# KegWasher_1_10_HCRelay_Schematic_EasyEDA.net
KiCad netlist of a schematic drawn in EasyEDA
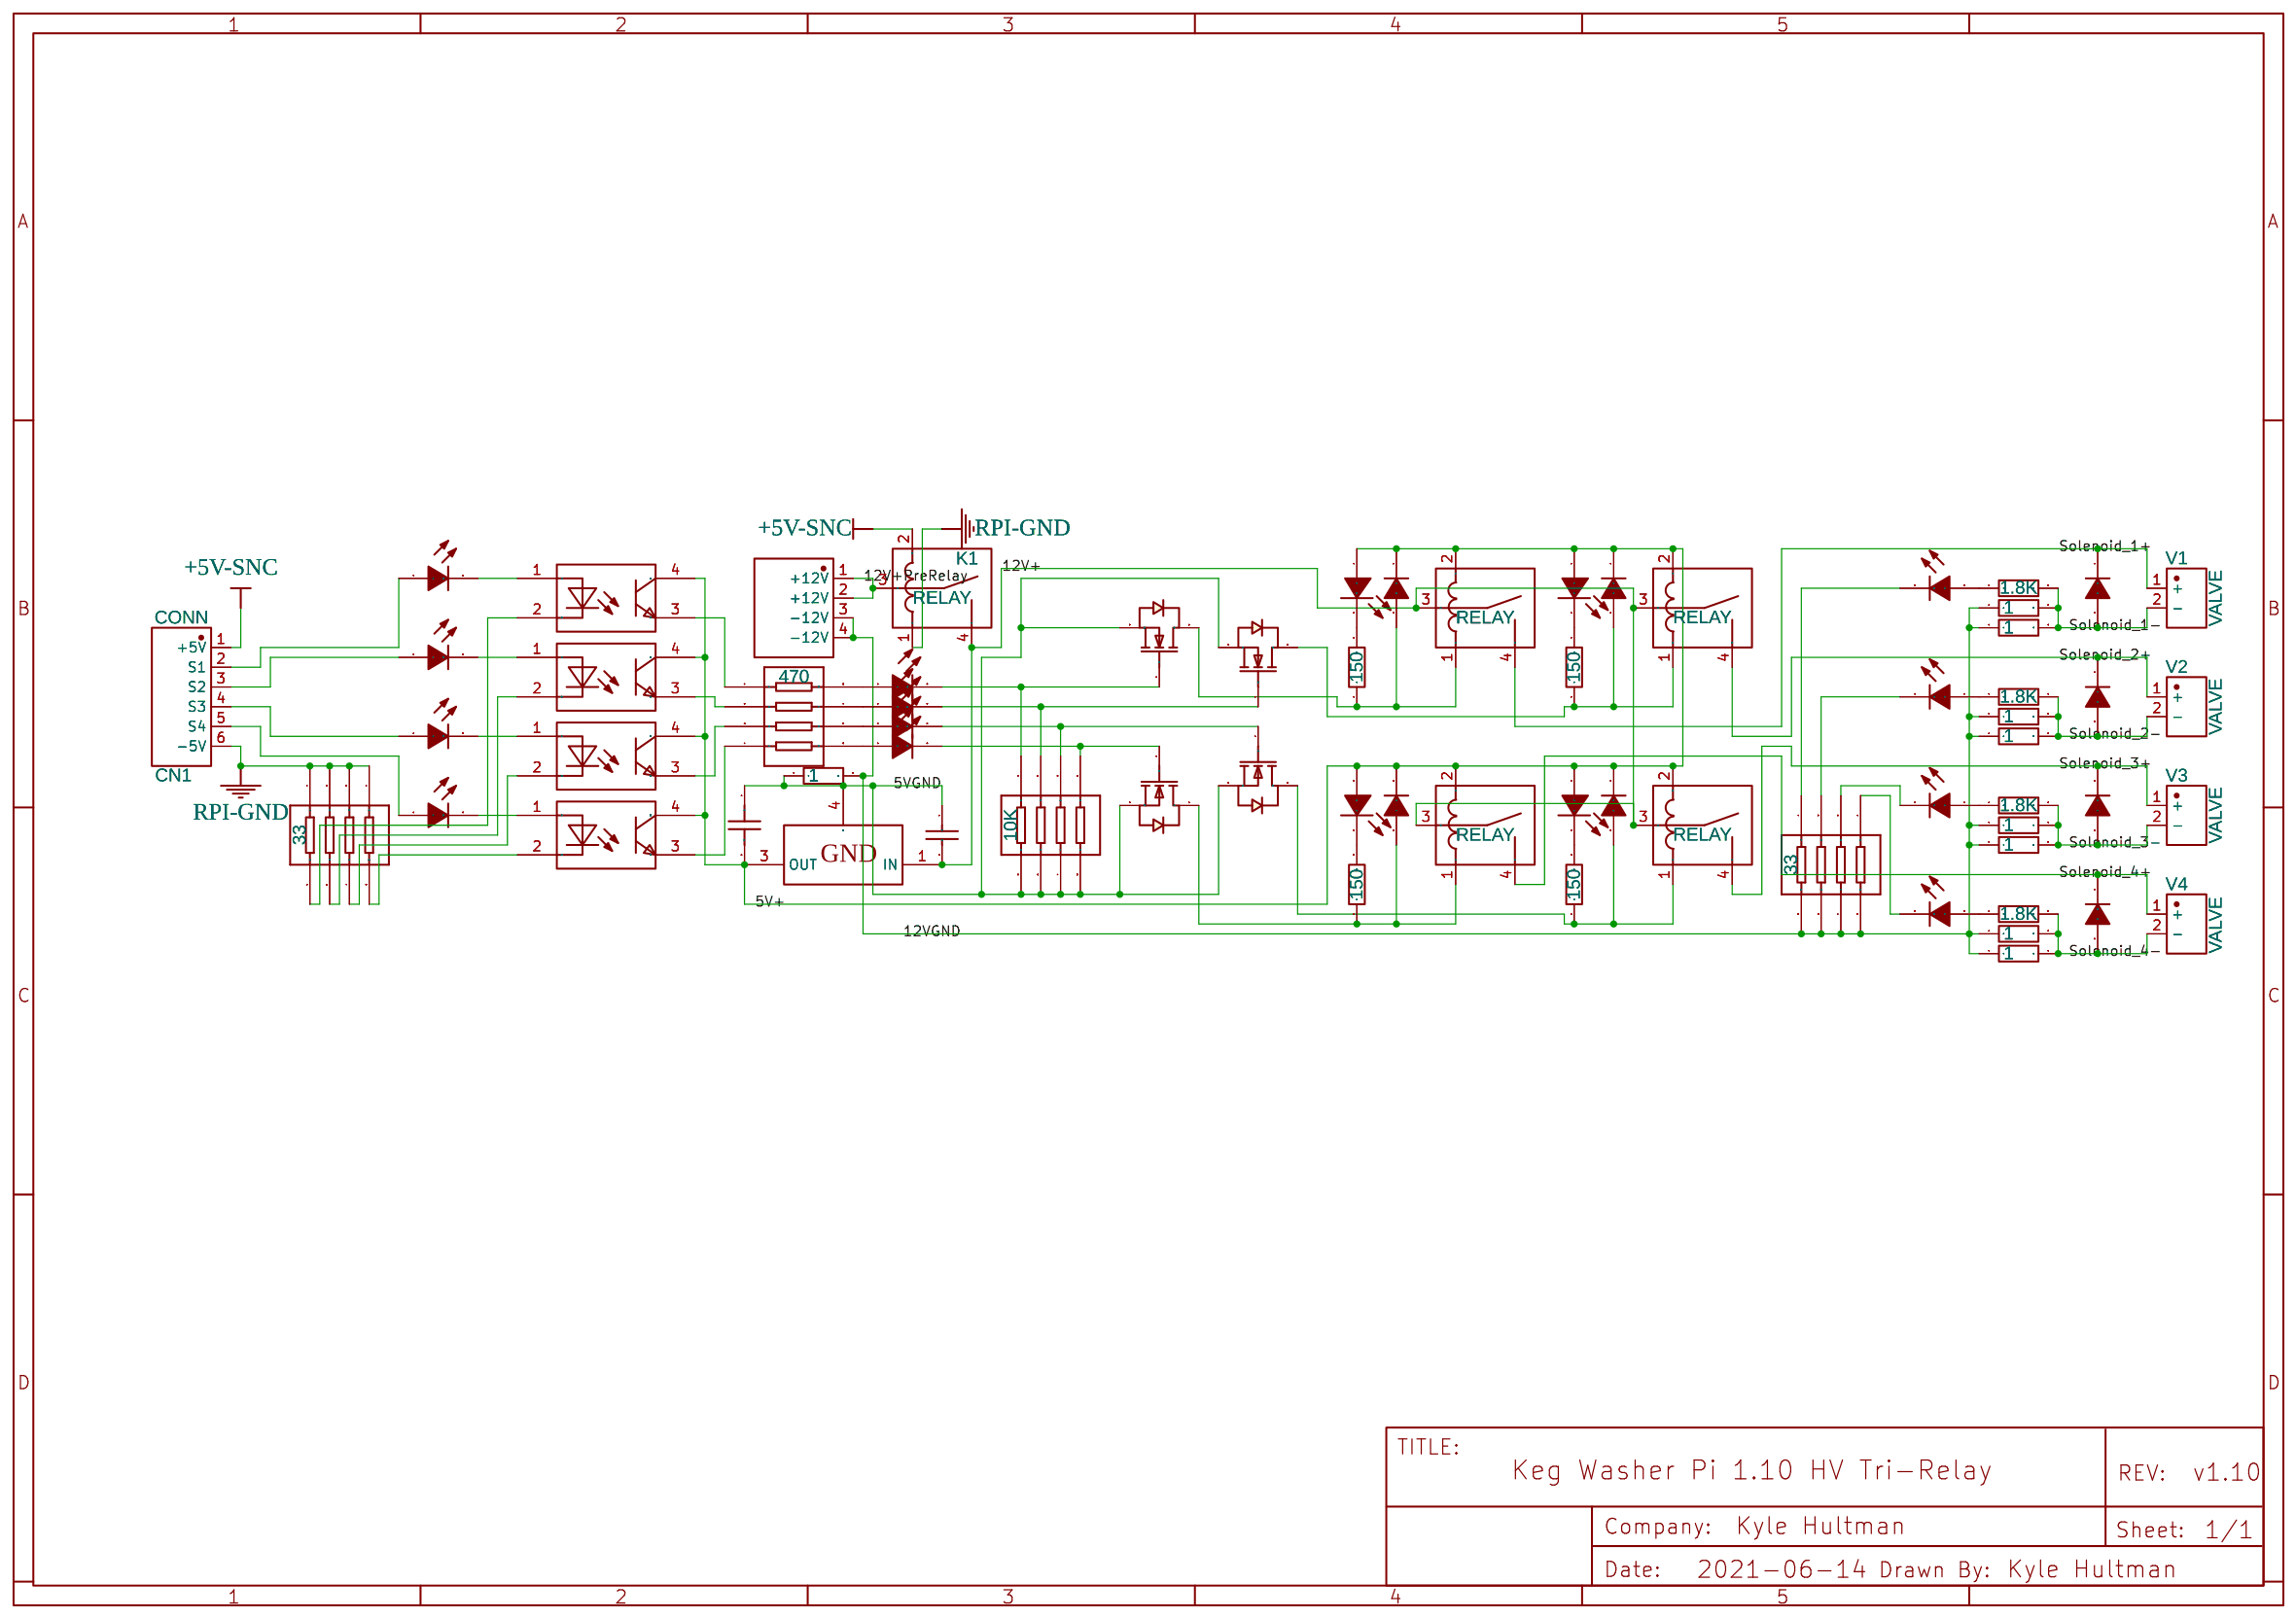
[diagram p0: schematic sheet]

(export (version "E")
  (design (tool "Eeschema 10.0.6"))
  (components
    (comp (ref "C1")
      (value "330nF")
      (fields
        (field (name "BOM_Manufacturer Part") "0805B334K500NT")
        (field (name "BOM_Supplier Part") "C1740")
      )
      (libsource (lib "") (part "0805B334K500NT"))
    )
    (comp (ref "C2")
      (value "100nF")
      (fields
        (field (name "BOM_Manufacturer Part") "CC0603KRX7R9BB104")
        (field (name "BOM_Supplier Part") "C14663")
      )
      (libsource (lib "") (part "CC0603KRX7R9BB104"))
    )
    (comp (ref "CN1") (value "CONN") (libsource (lib "") (part "CONN")))
    (comp (ref "D1")
      (value "1N4148WS T4")
      (fields (field (name "BOM_Supplier Part") "C2128"))
      (libsource (lib "") (part "1N4148WS T4"))
    )
    (comp (ref "D2")
      (value "1N4148WS T4")
      (fields (field (name "BOM_Supplier Part") "C2128"))
      (libsource (lib "") (part "1N4148WS T4"))
    )
    (comp (ref "D3")
      (value "1N4148WS T4")
      (fields (field (name "BOM_Supplier Part") "C2128"))
      (libsource (lib "") (part "1N4148WS T4"))
    )
    (comp (ref "D4")
      (value "1N4148WS T4")
      (fields (field (name "BOM_Supplier Part") "C2128"))
      (libsource (lib "") (part "1N4148WS T4"))
    )
    (comp (ref "D5")
      (value "1N4148WS T4")
      (fields (field (name "BOM_Supplier Part") "C2128"))
      (libsource (lib "") (part "1N4148WS T4"))
    )
    (comp (ref "D6")
      (value "1N4148WS T4")
      (fields (field (name "BOM_Supplier Part") "C2128"))
      (libsource (lib "") (part "1N4148WS T4"))
    )
    (comp (ref "D7")
      (value "1N4148WS T4")
      (fields (field (name "BOM_Supplier Part") "C2128"))
      (libsource (lib "") (part "1N4148WS T4"))
    )
    (comp (ref "D8")
      (value "1N4148WS T4")
      (fields (field (name "BOM_Supplier Part") "C2128"))
      (libsource (lib "") (part "1N4148WS T4"))
    )
    (comp (ref "K1")
      (value "RELAY")
      (fields
        (field (name "BOM_Manufacturer Part") "CMA51H-S-DC5V-A")
        (field (name "BOM_Supplier Part") "C125687")
      )
      (libsource (lib "") (part "CMA51H-S-DC5V-A"))
    )
    (comp (ref "K2")
      (value "RELAY")
      (fields
        (field (name "BOM_Manufacturer Part") "CMA51H-S-DC5V-A")
        (field (name "BOM_Supplier Part") "C125687")
      )
      (libsource (lib "") (part "CMA51H-S-DC5V-A"))
    )
    (comp (ref "K3")
      (value "RELAY")
      (fields
        (field (name "BOM_Manufacturer Part") "CMA51H-S-DC5V-A")
        (field (name "BOM_Supplier Part") "C125687")
      )
      (libsource (lib "") (part "CMA51H-S-DC5V-A"))
    )
    (comp (ref "K4")
      (value "RELAY")
      (fields
        (field (name "BOM_Manufacturer Part") "CMA51H-S-DC5V-A")
        (field (name "BOM_Supplier Part") "C125687")
      )
      (libsource (lib "") (part "CMA51H-S-DC5V-A"))
    )
    (comp (ref "K5")
      (value "RELAY")
      (fields
        (field (name "BOM_Manufacturer Part") "CMA51H-S-DC5V-A")
        (field (name "BOM_Supplier Part") "C125687")
      )
      (libsource (lib "") (part "CMA51H-S-DC5V-A"))
    )
    (comp (ref "LED1")
      (value "19-217/GHC-YR1S2/3T")
      (fields (field (name "BOM_Supplier Part") "C72043"))
      (libsource (lib "") (part "19-217/GHC-YR1S2/3T"))
    )
    (comp (ref "LED2")
      (value "19-217/GHC-YR1S2/3T")
      (fields (field (name "BOM_Supplier Part") "C72043"))
      (libsource (lib "") (part "19-217/GHC-YR1S2/3T"))
    )
    (comp (ref "LED3")
      (value "19-217/GHC-YR1S2/3T")
      (fields (field (name "BOM_Supplier Part") "C72043"))
      (libsource (lib "") (part "19-217/GHC-YR1S2/3T"))
    )
    (comp (ref "LED4")
      (value "19-217/GHC-YR1S2/3T")
      (fields (field (name "BOM_Supplier Part") "C72043"))
      (libsource (lib "") (part "19-217/GHC-YR1S2/3T"))
    )
    (comp (ref "LED5")
      (value "19-213/Y2C-CQ2R2L/3T(CY)")
      (fields (field (name "BOM_Supplier Part") "C72038"))
      (libsource (lib "") (part "19-213/Y2C-CQ2R2L/3T(CY)"))
    )
    (comp (ref "LED6")
      (value "19-213/Y2C-CQ2R2L/3T(CY)")
      (fields (field (name "BOM_Supplier Part") "C72038"))
      (libsource (lib "") (part "19-213/Y2C-CQ2R2L/3T(CY)"))
    )
    (comp (ref "LED7")
      (value "19-213/Y2C-CQ2R2L/3T(CY)")
      (fields (field (name "BOM_Supplier Part") "C72038"))
      (libsource (lib "") (part "19-213/Y2C-CQ2R2L/3T(CY)"))
    )
    (comp (ref "LED8")
      (value "19-213/Y2C-CQ2R2L/3T(CY)")
      (fields (field (name "BOM_Supplier Part") "C72038"))
      (libsource (lib "") (part "19-213/Y2C-CQ2R2L/3T(CY)"))
    )
    (comp (ref "LED9")
      (value "KT-0603R")
      (fields (field (name "BOM_Supplier Part") "C2286"))
      (libsource (lib "") (part "KT-0603R"))
    )
    (comp (ref "LED10")
      (value "KT-0603R")
      (fields (field (name "BOM_Supplier Part") "C2286"))
      (libsource (lib "") (part "KT-0603R"))
    )
    (comp (ref "LED11")
      (value "KT-0603R")
      (fields (field (name "BOM_Supplier Part") "C2286"))
      (libsource (lib "") (part "KT-0603R"))
    )
    (comp (ref "LED12")
      (value "KT-0603R")
      (fields (field (name "BOM_Supplier Part") "C2286"))
      (libsource (lib "") (part "KT-0603R"))
    )
    (comp (ref "LED13")
      (value "19-217/BHC-ZL1M2RY/3T")
      (fields (field (name "BOM_Supplier Part") "C72041"))
      (libsource (lib "") (part "19-217/BHC-ZL1M2RY/3T"))
    )
    (comp (ref "LED14")
      (value "19-217/BHC-ZL1M2RY/3T")
      (fields (field (name "BOM_Supplier Part") "C72041"))
      (libsource (lib "") (part "19-217/BHC-ZL1M2RY/3T"))
    )
    (comp (ref "LED15")
      (value "19-217/BHC-ZL1M2RY/3T")
      (fields (field (name "BOM_Supplier Part") "C72041"))
      (libsource (lib "") (part "19-217/BHC-ZL1M2RY/3T"))
    )
    (comp (ref "LED16")
      (value "19-217/BHC-ZL1M2RY/3T")
      (fields (field (name "BOM_Supplier Part") "C72041"))
      (libsource (lib "") (part "19-217/BHC-ZL1M2RY/3T"))
    )
    (comp (ref "PWR1") (value "12vHC-IN") (libsource (lib "") (part "12vHC-IN")))
    (comp (ref "Q1")
      (value "AO3400A")
      (fields (field (name "BOM_Supplier Part") "C20917"))
      (libsource (lib "") (part "AO3400A_1"))
    )
    (comp (ref "Q2")
      (value "AO3400A")
      (fields (field (name "BOM_Supplier Part") "C20917"))
      (libsource (lib "") (part "AO3400A_1"))
    )
    (comp (ref "Q3")
      (value "AO3400A")
      (fields (field (name "BOM_Supplier Part") "C20917"))
      (libsource (lib "") (part "AO3400A"))
    )
    (comp (ref "Q4")
      (value "AO3400A")
      (fields (field (name "BOM_Supplier Part") "C20917"))
      (libsource (lib "") (part "AO3400A"))
    )
    (comp (ref "R1")
      (value "150")
      (fields
        (field (name "BOM_Manufacturer Part") "0603WAF1500T5E")
        (field (name "BOM_Supplier Part") "C22808")
      )
      (libsource (lib "") (part "0603WAF1500T5E"))
    )
    (comp (ref "R2")
      (value "150")
      (fields
        (field (name "BOM_Manufacturer Part") "0603WAF1500T5E")
        (field (name "BOM_Supplier Part") "C22808")
      )
      (libsource (lib "") (part "0603WAF1500T5E"))
    )
    (comp (ref "R3")
      (value "150")
      (fields
        (field (name "BOM_Manufacturer Part") "0603WAF1500T5E")
        (field (name "BOM_Supplier Part") "C22808")
      )
      (libsource (lib "") (part "0603WAF1500T5E"))
    )
    (comp (ref "R4")
      (value "150")
      (fields
        (field (name "BOM_Manufacturer Part") "0603WAF1500T5E")
        (field (name "BOM_Supplier Part") "C22808")
      )
      (libsource (lib "") (part "0603WAF1500T5E"))
    )
    (comp (ref "R5")
      (value "1.8K")
      (fields
        (field (name "BOM_Manufacturer Part") "0805W8F1801T5E")
        (field (name "BOM_Supplier Part") "C17398")
      )
      (libsource (lib "") (part "0805W8F1801T5E"))
    )
    (comp (ref "R6")
      (value "1.8K")
      (fields
        (field (name "BOM_Manufacturer Part") "0805W8F1801T5E")
        (field (name "BOM_Supplier Part") "C17398")
      )
      (libsource (lib "") (part "0805W8F1801T5E"))
    )
    (comp (ref "R7")
      (value "1.8K")
      (fields
        (field (name "BOM_Manufacturer Part") "0805W8F1801T5E")
        (field (name "BOM_Supplier Part") "C17398")
      )
      (libsource (lib "") (part "0805W8F1801T5E"))
    )
    (comp (ref "R8")
      (value "1.8K")
      (fields
        (field (name "BOM_Manufacturer Part") "0805W8F1801T5E")
        (field (name "BOM_Supplier Part") "C17398")
      )
      (libsource (lib "") (part "0805W8F1801T5E"))
    )
    (comp (ref "R9")
      (value "1")
      (fields
        (field (name "BOM_Manufacturer Part") "1206W4F100KT5E")
        (field (name "BOM_Supplier Part") "C17928")
      )
      (libsource (lib "") (part "1206W4F100KT5E"))
    )
    (comp (ref "R10")
      (value "1")
      (fields
        (field (name "BOM_Manufacturer Part") "1206W4F100KT5E")
        (field (name "BOM_Supplier Part") "C17928")
      )
      (libsource (lib "") (part "1206W4F100KT5E"))
    )
    (comp (ref "R11")
      (value "1")
      (fields
        (field (name "BOM_Manufacturer Part") "1206W4F100KT5E")
        (field (name "BOM_Supplier Part") "C17928")
      )
      (libsource (lib "") (part "1206W4F100KT5E"))
    )
    (comp (ref "R12")
      (value "1")
      (fields
        (field (name "BOM_Manufacturer Part") "1206W4F100KT5E")
        (field (name "BOM_Supplier Part") "C17928")
      )
      (libsource (lib "") (part "1206W4F100KT5E"))
    )
    (comp (ref "R13")
      (value "1")
      (fields
        (field (name "BOM_Manufacturer Part") "1206W4F100KT5E")
        (field (name "BOM_Supplier Part") "C17928")
      )
      (libsource (lib "") (part "1206W4F100KT5E"))
    )
    (comp (ref "R14")
      (value "1")
      (fields
        (field (name "BOM_Manufacturer Part") "1206W4F100KT5E")
        (field (name "BOM_Supplier Part") "C17928")
      )
      (libsource (lib "") (part "1206W4F100KT5E"))
    )
    (comp (ref "R15")
      (value "1")
      (fields
        (field (name "BOM_Manufacturer Part") "1206W4F100KT5E")
        (field (name "BOM_Supplier Part") "C17928")
      )
      (libsource (lib "") (part "1206W4F100KT5E"))
    )
    (comp (ref "R16")
      (value "1")
      (fields
        (field (name "BOM_Manufacturer Part") "1206W4F100KT5E")
        (field (name "BOM_Supplier Part") "C17928")
      )
      (libsource (lib "") (part "1206W4F100KT5E"))
    )
    (comp (ref "R17")
      (value "1")
      (fields
        (field (name "BOM_Manufacturer Part") "1206W4F100KT5E")
        (field (name "BOM_Supplier Part") "C17928")
      )
      (libsource (lib "") (part "1206W4F100KT5E"))
    )
    (comp (ref "RN1")
      (value "33")
      (fields
        (field (name "BOM_Manufacturer Part") "4D02WGJ0330TCE")
        (field (name "BOM_Supplier Part") "C25501")
      )
      (libsource (lib "") (part "4D02WGJ0330TCE"))
    )
    (comp (ref "RN2")
      (value "470")
      (fields
        (field (name "BOM_Manufacturer Part") "4D03WGJ0471T5E")
        (field (name "BOM_Supplier Part") "C25510")
      )
      (libsource (lib "") (part "4D03WGJ0471T5E"))
    )
    (comp (ref "RN3")
      (value "10K")
      (fields
        (field (name "BOM_Manufacturer Part") "4D02WGJ0103TCE")
        (field (name "BOM_Supplier Part") "C25725")
      )
      (libsource (lib "") (part "4D02WGJ0103TCE"))
    )
    (comp (ref "RN4")
      (value "33")
      (fields
        (field (name "BOM_Manufacturer Part") "4D02WGJ0330TCE")
        (field (name "BOM_Supplier Part") "C25501")
      )
      (libsource (lib "") (part "4D02WGJ0330TCE"))
    )
    (comp (ref "U1")
      (value "EL357N(B)(TA)-G")
      (fields (field (name "BOM_Supplier Part") "C6649"))
      (libsource (lib "") (part "EL357N(B)(TA)-G"))
    )
    (comp (ref "U2")
      (value "EL357N(B)(TA)-G")
      (fields (field (name "BOM_Supplier Part") "C6649"))
      (libsource (lib "") (part "EL357N(B)(TA)-G"))
    )
    (comp (ref "U3")
      (value "EL357N(B)(TA)-G")
      (fields (field (name "BOM_Supplier Part") "C6649"))
      (libsource (lib "") (part "EL357N(B)(TA)-G"))
    )
    (comp (ref "U4")
      (value "EL357N(B)(TA)-G")
      (fields (field (name "BOM_Supplier Part") "C6649"))
      (libsource (lib "") (part "EL357N(B)(TA)-G"))
    )
    (comp (ref "U5")
      (value "L78M05ABDT-TR")
      (fields (field (name "BOM_Supplier Part") "C58069"))
      (libsource (lib "") (part "L78M05ABDT-TR"))
    )
    (comp (ref "V1") (value "VALVE") (libsource (lib "") (part "VALVE")))
    (comp (ref "V2") (value "VALVE") (libsource (lib "") (part "VALVE")))
    (comp (ref "V3") (value "VALVE") (libsource (lib "") (part "VALVE")))
    (comp (ref "V4") (value "VALVE") (libsource (lib "") (part "RELAY")))
  )
  (nets
    (net (code "1") (name "+5V-SNC") (class "Default")
      (node (ref "CN1") (pin "1") (pinfunction "+5V_1") (pintype "passive"))
      (node (ref "K1") (pin "2") (pinfunction "2_2") (pintype "unspecified"))
    )
    (net (code "2") (name "/5V+") (class "Default")
      (node (ref "C2") (pin "2") (pinfunction "2_2") (pintype "unspecified"))
      (node (ref "D1") (pin "1") (pinfunction "K_1") (pintype "unspecified"))
      (node (ref "D2") (pin "1") (pinfunction "K_1") (pintype "unspecified"))
      (node (ref "D3") (pin "1") (pinfunction "K_1") (pintype "unspecified"))
      (node (ref "D4") (pin "1") (pinfunction "K_1") (pintype "unspecified"))
      (node (ref "K2") (pin "2") (pinfunction "2_2") (pintype "unspecified"))
      (node (ref "K3") (pin "2") (pinfunction "2_2") (pintype "unspecified"))
      (node (ref "K4") (pin "2") (pinfunction "2_2") (pintype "unspecified"))
      (node (ref "K5") (pin "2") (pinfunction "2_2") (pintype "unspecified"))
      (node (ref "LED10") (pin "1") (pinfunction "A_1") (pintype "unspecified"))
      (node (ref "LED11") (pin "1") (pinfunction "A_1") (pintype "unspecified"))
      (node (ref "LED12") (pin "1") (pinfunction "A_1") (pintype "unspecified"))
      (node (ref "LED9") (pin "1") (pinfunction "A_1") (pintype "unspecified"))
      (node (ref "U1") (pin "4") (pinfunction "COL_4") (pintype "unspecified"))
      (node (ref "U2") (pin "4") (pinfunction "COL_4") (pintype "unspecified"))
      (node (ref "U3") (pin "4") (pinfunction "COL_4") (pintype "unspecified"))
      (node (ref "U4") (pin "4") (pinfunction "COL_4") (pintype "unspecified"))
      (node (ref "U5") (pin "3") (pinfunction "OUT_3") (pintype "passive"))
    )
    (net (code "3") (name "/5VGND") (class "Default")
      (node (ref "C1") (pin "1") (pinfunction "1_1") (pintype "input"))
      (node (ref "C2") (pin "1") (pinfunction "1_1") (pintype "unspecified"))
      (node (ref "Q1") (pin "2") (pinfunction "S_2") (pintype "unspecified"))
      (node (ref "Q2") (pin "2") (pinfunction "S_2") (pintype "unspecified"))
      (node (ref "Q3") (pin "2") (pinfunction "S_2") (pintype "unspecified"))
      (node (ref "Q4") (pin "2") (pinfunction "S_2") (pintype "unspecified"))
      (node (ref "R17") (pin "1") (pinfunction "1_1") (pintype "input"))
      (node (ref "RN3") (pin "5") (pinfunction "5_5") (pintype "input"))
      (node (ref "RN3") (pin "6") (pinfunction "6_6") (pintype "input"))
      (node (ref "RN3") (pin "7") (pinfunction "7_7") (pintype "input"))
      (node (ref "RN3") (pin "8") (pinfunction "8_8") (pintype "input"))
      (node (ref "U5") (pin "4") (pinfunction "GND_4") (pintype "passive"))
    )
    (net (code "4") (name "/12V+") (class "Default")
      (node (ref "C1") (pin "2") (pinfunction "2_2") (pintype "input"))
      (node (ref "K1") (pin "4") (pinfunction "4_4") (pintype "unspecified"))
      (node (ref "K2") (pin "3") (pinfunction "3_3") (pintype "unspecified"))
      (node (ref "K3") (pin "3") (pinfunction "3_3") (pintype "unspecified"))
      (node (ref "K4") (pin "3") (pinfunction "3_3") (pintype "unspecified"))
      (node (ref "K5") (pin "3") (pinfunction "3_3") (pintype "unspecified"))
      (node (ref "U5") (pin "1") (pinfunction "IN_1") (pintype "passive"))
    )
    (net (code "5") (name "/12V+PreRelay") (class "Default")
      (node (ref "K1") (pin "3") (pinfunction "3_3") (pintype "unspecified"))
      (node (ref "PWR1") (pin "1") (pinfunction "+12V_1") (pintype "passive"))
      (node (ref "PWR1") (pin "2") (pinfunction "+12V_2") (pintype "passive"))
    )
    (net (code "6") (name "/12VGND") (class "Default")
      (node (ref "PWR1") (pin "3") (pinfunction "-12V_3") (pintype "passive"))
      (node (ref "PWR1") (pin "4") (pinfunction "-12V_4") (pintype "passive"))
      (node (ref "R10") (pin "1") (pinfunction "1_1") (pintype "input"))
      (node (ref "R11") (pin "1") (pinfunction "1_1") (pintype "input"))
      (node (ref "R12") (pin "1") (pinfunction "1_1") (pintype "input"))
      (node (ref "R13") (pin "1") (pinfunction "1_1") (pintype "input"))
      (node (ref "R14") (pin "1") (pinfunction "1_1") (pintype "input"))
      (node (ref "R15") (pin "1") (pinfunction "1_1") (pintype "input"))
      (node (ref "R16") (pin "1") (pinfunction "1_1") (pintype "input"))
      (node (ref "R17") (pin "2") (pinfunction "2_2") (pintype "input"))
      (node (ref "R9") (pin "1") (pinfunction "1_1") (pintype "input"))
      (node (ref "RN4") (pin "5") (pinfunction "5_5") (pintype "input"))
      (node (ref "RN4") (pin "6") (pinfunction "6_6") (pintype "input"))
      (node (ref "RN4") (pin "7") (pinfunction "7_7") (pintype "input"))
      (node (ref "RN4") (pin "8") (pinfunction "8_8") (pintype "input"))
    )
    (net (code "7") (name "/Solenoid_1+") (class "Default")
      (node (ref "D5") (pin "1") (pinfunction "K_1") (pintype "unspecified"))
      (node (ref "K2") (pin "4") (pinfunction "4_4") (pintype "unspecified"))
      (node (ref "V1") (pin "1") (pinfunction "+_1") (pintype "passive"))
    )
    (net (code "8") (name "/Solenoid_1-") (class "Default")
      (node (ref "D5") (pin "2") (pinfunction "A_2") (pintype "unspecified"))
      (node (ref "R10") (pin "2") (pinfunction "2_2") (pintype "input"))
      (node (ref "R5") (pin "2") (pinfunction "2_2") (pintype "input"))
      (node (ref "R9") (pin "2") (pinfunction "2_2") (pintype "input"))
      (node (ref "V1") (pin "2") (pinfunction "-_2") (pintype "passive"))
    )
    (net (code "9") (name "/Solenoid_2+") (class "Default")
      (node (ref "D6") (pin "1") (pinfunction "K_1") (pintype "unspecified"))
      (node (ref "K3") (pin "4") (pinfunction "4_4") (pintype "unspecified"))
      (node (ref "V2") (pin "1") (pinfunction "+_1") (pintype "passive"))
    )
    (net (code "10") (name "/Solenoid_2-") (class "Default")
      (node (ref "D6") (pin "2") (pinfunction "A_2") (pintype "unspecified"))
      (node (ref "R11") (pin "2") (pinfunction "2_2") (pintype "input"))
      (node (ref "R12") (pin "2") (pinfunction "2_2") (pintype "input"))
      (node (ref "R6") (pin "2") (pinfunction "2_2") (pintype "input"))
      (node (ref "V2") (pin "2") (pinfunction "-_2") (pintype "passive"))
    )
    (net (code "11") (name "/Solenoid_3+") (class "Default")
      (node (ref "D7") (pin "1") (pinfunction "K_1") (pintype "unspecified"))
      (node (ref "K4") (pin "4") (pinfunction "4_4") (pintype "unspecified"))
      (node (ref "V3") (pin "1") (pinfunction "+_1") (pintype "passive"))
    )
    (net (code "12") (name "/Solenoid_3-") (class "Default")
      (node (ref "D7") (pin "2") (pinfunction "A_2") (pintype "unspecified"))
      (node (ref "R13") (pin "2") (pinfunction "2_2") (pintype "input"))
      (node (ref "R14") (pin "2") (pinfunction "2_2") (pintype "input"))
      (node (ref "R7") (pin "2") (pinfunction "2_2") (pintype "input"))
      (node (ref "V3") (pin "2") (pinfunction "-_2") (pintype "passive"))
    )
    (net (code "13") (name "/Solenoid_4+") (class "Default")
      (node (ref "D8") (pin "1") (pinfunction "K_1") (pintype "unspecified"))
      (node (ref "K5") (pin "4") (pinfunction "4_4") (pintype "unspecified"))
      (node (ref "V4") (pin "1") (pinfunction "+_1") (pintype "passive"))
    )
    (net (code "14") (name "/Solenoid_4-") (class "Default")
      (node (ref "D8") (pin "2") (pinfunction "A_2") (pintype "unspecified"))
      (node (ref "R15") (pin "2") (pinfunction "2_2") (pintype "input"))
      (node (ref "R16") (pin "2") (pinfunction "2_2") (pintype "input"))
      (node (ref "R8") (pin "2") (pinfunction "2_2") (pintype "input"))
      (node (ref "V4") (pin "2") (pinfunction "-_2") (pintype "passive"))
    )
    (net (code "15") (name "Net-(CN1-S1)") (class "Default")
      (node (ref "CN1") (pin "2") (pinfunction "S1_2") (pintype "input"))
      (node (ref "LED1") (pin "1") (pinfunction "A_1") (pintype "input"))
    )
    (net (code "16") (name "Net-(CN1-S2)") (class "Default")
      (node (ref "CN1") (pin "3") (pinfunction "S2_3") (pintype "input"))
      (node (ref "LED2") (pin "1") (pinfunction "A_1") (pintype "input"))
    )
    (net (code "17") (name "Net-(CN1-S3)") (class "Default")
      (node (ref "CN1") (pin "4") (pinfunction "S3_4") (pintype "input"))
      (node (ref "LED3") (pin "1") (pinfunction "A_1") (pintype "input"))
    )
    (net (code "18") (name "Net-(CN1-S4)") (class "Default")
      (node (ref "CN1") (pin "5") (pinfunction "S4_5") (pintype "input"))
      (node (ref "LED4") (pin "1") (pinfunction "A_1") (pintype "input"))
    )
    (net (code "19") (name "Net-(D1-A)") (class "Default")
      (node (ref "D1") (pin "2") (pinfunction "A_2") (pintype "unspecified"))
      (node (ref "K2") (pin "1") (pinfunction "1_1") (pintype "unspecified"))
      (node (ref "Q1") (pin "3") (pinfunction "D_3") (pintype "unspecified"))
      (node (ref "R1") (pin "1") (pinfunction "1_1") (pintype "input"))
    )
    (net (code "20") (name "Net-(D2-A)") (class "Default")
      (node (ref "D2") (pin "2") (pinfunction "A_2") (pintype "unspecified"))
      (node (ref "K3") (pin "1") (pinfunction "1_1") (pintype "unspecified"))
      (node (ref "Q2") (pin "3") (pinfunction "D_3") (pintype "unspecified"))
      (node (ref "R2") (pin "1") (pinfunction "1_1") (pintype "input"))
    )
    (net (code "21") (name "Net-(D3-A)") (class "Default")
      (node (ref "D3") (pin "2") (pinfunction "A_2") (pintype "unspecified"))
      (node (ref "K4") (pin "1") (pinfunction "1_1") (pintype "unspecified"))
      (node (ref "Q3") (pin "3") (pinfunction "D_3") (pintype "unspecified"))
      (node (ref "R3") (pin "1") (pinfunction "1_1") (pintype "input"))
    )
    (net (code "22") (name "Net-(D4-A)") (class "Default")
      (node (ref "D4") (pin "2") (pinfunction "A_2") (pintype "unspecified"))
      (node (ref "K5") (pin "1") (pinfunction "1_1") (pintype "unspecified"))
      (node (ref "Q4") (pin "3") (pinfunction "D_3") (pintype "unspecified"))
      (node (ref "R4") (pin "1") (pinfunction "1_1") (pintype "input"))
    )
    (net (code "23") (name "Net-(LED1-C)") (class "Default")
      (node (ref "LED1") (pin "2") (pinfunction "C_2") (pintype "input"))
      (node (ref "U1") (pin "1") (pinfunction "AN_1") (pintype "unspecified"))
    )
    (net (code "24") (name "Net-(LED2-C)") (class "Default")
      (node (ref "LED2") (pin "2") (pinfunction "C_2") (pintype "input"))
      (node (ref "U2") (pin "1") (pinfunction "AN_1") (pintype "unspecified"))
    )
    (net (code "25") (name "Net-(LED3-C)") (class "Default")
      (node (ref "LED3") (pin "2") (pinfunction "C_2") (pintype "input"))
      (node (ref "U3") (pin "1") (pinfunction "AN_1") (pintype "unspecified"))
    )
    (net (code "26") (name "Net-(LED4-C)") (class "Default")
      (node (ref "LED4") (pin "2") (pinfunction "C_2") (pintype "input"))
      (node (ref "U4") (pin "1") (pinfunction "AN_1") (pintype "unspecified"))
    )
    (net (code "27") (name "Net-(LED5-A)") (class "Default")
      (node (ref "LED5") (pin "1") (pinfunction "A_1") (pintype "input"))
      (node (ref "RN2") (pin "8") (pinfunction "8_8") (pintype "input"))
    )
    (net (code "28") (name "Net-(LED5-C)") (class "Default")
      (node (ref "LED5") (pin "2") (pinfunction "C_2") (pintype "input"))
      (node (ref "Q1") (pin "1") (pinfunction "G_1") (pintype "unspecified"))
      (node (ref "RN3") (pin "4") (pinfunction "4_4") (pintype "input"))
    )
    (net (code "29") (name "Net-(LED6-A)") (class "Default")
      (node (ref "LED6") (pin "1") (pinfunction "A_1") (pintype "input"))
      (node (ref "RN2") (pin "7") (pinfunction "7_7") (pintype "input"))
    )
    (net (code "30") (name "Net-(LED6-C)") (class "Default")
      (node (ref "LED6") (pin "2") (pinfunction "C_2") (pintype "input"))
      (node (ref "Q2") (pin "1") (pinfunction "G_1") (pintype "unspecified"))
      (node (ref "RN3") (pin "3") (pinfunction "3_3") (pintype "input"))
    )
    (net (code "31") (name "Net-(LED7-A)") (class "Default")
      (node (ref "LED7") (pin "1") (pinfunction "A_1") (pintype "input"))
      (node (ref "RN2") (pin "6") (pinfunction "6_6") (pintype "input"))
    )
    (net (code "32") (name "Net-(LED7-C)") (class "Default")
      (node (ref "LED7") (pin "2") (pinfunction "C_2") (pintype "input"))
      (node (ref "Q3") (pin "1") (pinfunction "G_1") (pintype "unspecified"))
      (node (ref "RN3") (pin "2") (pinfunction "2_2") (pintype "input"))
    )
    (net (code "33") (name "Net-(LED8-A)") (class "Default")
      (node (ref "LED8") (pin "1") (pinfunction "A_1") (pintype "input"))
      (node (ref "RN2") (pin "5") (pinfunction "5_5") (pintype "input"))
    )
    (net (code "34") (name "Net-(LED8-C)") (class "Default")
      (node (ref "LED8") (pin "2") (pinfunction "C_2") (pintype "input"))
      (node (ref "Q4") (pin "1") (pinfunction "G_1") (pintype "unspecified"))
      (node (ref "RN3") (pin "1") (pinfunction "1_1") (pintype "input"))
    )
    (net (code "35") (name "Net-(LED9-K)") (class "Default")
      (node (ref "LED9") (pin "2") (pinfunction "K_2") (pintype "unspecified"))
      (node (ref "R1") (pin "2") (pinfunction "2_2") (pintype "input"))
    )
    (net (code "36") (name "Net-(LED10-K)") (class "Default")
      (node (ref "LED10") (pin "2") (pinfunction "K_2") (pintype "unspecified"))
      (node (ref "R2") (pin "2") (pinfunction "2_2") (pintype "input"))
    )
    (net (code "37") (name "Net-(LED11-K)") (class "Default")
      (node (ref "LED11") (pin "2") (pinfunction "K_2") (pintype "unspecified"))
      (node (ref "R3") (pin "2") (pinfunction "2_2") (pintype "input"))
    )
    (net (code "38") (name "Net-(LED12-K)") (class "Default")
      (node (ref "LED12") (pin "2") (pinfunction "K_2") (pintype "unspecified"))
      (node (ref "R4") (pin "2") (pinfunction "2_2") (pintype "input"))
    )
    (net (code "39") (name "Net-(LED13-A)") (class "Default")
      (node (ref "LED13") (pin "1") (pinfunction "A_1") (pintype "input"))
      (node (ref "R5") (pin "1") (pinfunction "1_1") (pintype "input"))
    )
    (net (code "40") (name "Net-(LED13-C)") (class "Default")
      (node (ref "LED13") (pin "2") (pinfunction "C_2") (pintype "input"))
      (node (ref "RN4") (pin "4") (pinfunction "4_4") (pintype "input"))
    )
    (net (code "41") (name "Net-(LED14-A)") (class "Default")
      (node (ref "LED14") (pin "1") (pinfunction "A_1") (pintype "input"))
      (node (ref "R6") (pin "1") (pinfunction "1_1") (pintype "input"))
    )
    (net (code "42") (name "Net-(LED14-C)") (class "Default")
      (node (ref "LED14") (pin "2") (pinfunction "C_2") (pintype "input"))
      (node (ref "RN4") (pin "3") (pinfunction "3_3") (pintype "input"))
    )
    (net (code "43") (name "Net-(LED15-A)") (class "Default")
      (node (ref "LED15") (pin "1") (pinfunction "A_1") (pintype "input"))
      (node (ref "R7") (pin "1") (pinfunction "1_1") (pintype "input"))
    )
    (net (code "44") (name "Net-(LED15-C)") (class "Default")
      (node (ref "LED15") (pin "2") (pinfunction "C_2") (pintype "input"))
      (node (ref "RN4") (pin "2") (pinfunction "2_2") (pintype "input"))
    )
    (net (code "45") (name "Net-(LED16-A)") (class "Default")
      (node (ref "LED16") (pin "1") (pinfunction "A_1") (pintype "input"))
      (node (ref "R8") (pin "1") (pinfunction "1_1") (pintype "input"))
    )
    (net (code "46") (name "Net-(LED16-C)") (class "Default")
      (node (ref "LED16") (pin "2") (pinfunction "C_2") (pintype "input"))
      (node (ref "RN4") (pin "1") (pinfunction "1_1") (pintype "input"))
    )
    (net (code "47") (name "Net-(U1-CAT)") (class "Default")
      (node (ref "RN1") (pin "5") (pinfunction "5_5") (pintype "input"))
      (node (ref "U1") (pin "2") (pinfunction "CAT_2") (pintype "unspecified"))
    )
    (net (code "48") (name "Net-(U1-EM)") (class "Default")
      (node (ref "RN2") (pin "1") (pinfunction "1_1") (pintype "input"))
      (node (ref "U1") (pin "3") (pinfunction "EM_3") (pintype "unspecified"))
    )
    (net (code "49") (name "Net-(U2-CAT)") (class "Default")
      (node (ref "RN1") (pin "6") (pinfunction "6_6") (pintype "input"))
      (node (ref "U2") (pin "2") (pinfunction "CAT_2") (pintype "unspecified"))
    )
    (net (code "50") (name "Net-(U2-EM)") (class "Default")
      (node (ref "RN2") (pin "2") (pinfunction "2_2") (pintype "input"))
      (node (ref "U2") (pin "3") (pinfunction "EM_3") (pintype "unspecified"))
    )
    (net (code "51") (name "Net-(U3-CAT)") (class "Default")
      (node (ref "RN1") (pin "7") (pinfunction "7_7") (pintype "input"))
      (node (ref "U3") (pin "2") (pinfunction "CAT_2") (pintype "unspecified"))
    )
    (net (code "52") (name "Net-(U3-EM)") (class "Default")
      (node (ref "RN2") (pin "3") (pinfunction "3_3") (pintype "input"))
      (node (ref "U3") (pin "3") (pinfunction "EM_3") (pintype "unspecified"))
    )
    (net (code "53") (name "Net-(U4-CAT)") (class "Default")
      (node (ref "RN1") (pin "8") (pinfunction "8_8") (pintype "input"))
      (node (ref "U4") (pin "2") (pinfunction "CAT_2") (pintype "unspecified"))
    )
    (net (code "54") (name "Net-(U4-EM)") (class "Default")
      (node (ref "RN2") (pin "4") (pinfunction "4_4") (pintype "input"))
      (node (ref "U4") (pin "3") (pinfunction "EM_3") (pintype "unspecified"))
    )
    (net (code "55") (name "RPI-GND") (class "Default")
      (node (ref "CN1") (pin "6") (pinfunction "-5V_6") (pintype "passive"))
      (node (ref "K1") (pin "1") (pinfunction "1_1") (pintype "unspecified"))
      (node (ref "RN1") (pin "1") (pinfunction "1_1") (pintype "input"))
      (node (ref "RN1") (pin "2") (pinfunction "2_2") (pintype "input"))
      (node (ref "RN1") (pin "3") (pinfunction "3_3") (pintype "input"))
      (node (ref "RN1") (pin "4") (pinfunction "4_4") (pintype "input"))
    )
  )
)
